# IMU.net
KiCad netlist of a schematic drawn in Altium Designer
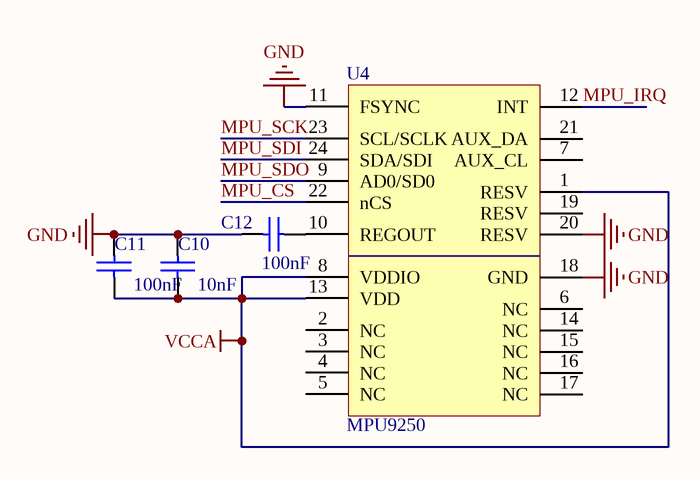
[diagram p0: IMU.SchDoc]

(export (version "E")
  (design (tool "Eeschema 10.0.6"))
  (components
    (comp (ref "C10")
      (value "10nF")
      (footprint "0402C")
      (description "贴片电阻")
      (libsource (lib "sparky") (part "cap"))
    )
    (comp (ref "C11")
      (value "100nF")
      (footprint "0402C")
      (description "贴片电阻")
      (libsource (lib "sparky") (part "cap"))
    )
    (comp (ref "C12")
      (value "100nF")
      (footprint "0402C")
      (description "贴片电阻")
      (libsource (lib "sparky") (part "cap"))
    )
    (comp (ref "U4") (value "MPU9250") (footprint "QFN24-0.4") (libsource (lib "MiniFly+") (part "MPU9250")))
  )
  (nets
    (net (code "1") (name "/MPU_CS") (class "Default")
      (node (ref "U4") (pin "22") (pinfunction "nCS_22") (pintype "passive"))
    )
    (net (code "2") (name "/MPU_IRQ") (class "Default")
      (node (ref "U4") (pin "12") (pinfunction "INT_12") (pintype "passive"))
    )
    (net (code "3") (name "/MPU_SCK") (class "Default")
      (node (ref "U4") (pin "23") (pinfunction "SCL/SCLK_23") (pintype "passive"))
    )
    (net (code "4") (name "/MPU_SDI") (class "Default")
      (node (ref "U4") (pin "24") (pinfunction "SDA/SDI_24") (pintype "passive"))
    )
    (net (code "5") (name "/MPU_SDO") (class "Default")
      (node (ref "U4") (pin "9") (pinfunction "AD0/SD0_9") (pintype "passive"))
    )
    (net (code "6") (name "GND") (class "Default")
      (node (ref "C10") (pin "2") (pinfunction "2_2") (pintype "passive"))
      (node (ref "C11") (pin "2") (pinfunction "2_2") (pintype "passive"))
      (node (ref "C12") (pin "1") (pinfunction "1_1") (pintype "passive"))
      (node (ref "U4") (pin "11") (pinfunction "FSYNC_11") (pintype "passive"))
      (node (ref "U4") (pin "18") (pinfunction "GND_18") (pintype "passive"))
      (node (ref "U4") (pin "20") (pinfunction "RESV_20") (pintype "passive"))
    )
    (net (code "7") (name "Net-(U4-REGOUT)") (class "Default")
      (node (ref "C12") (pin "2") (pinfunction "2_2") (pintype "passive"))
      (node (ref "U4") (pin "10") (pinfunction "REGOUT_10") (pintype "passive"))
    )
    (net (code "8") (name "VCCA") (class "Default")
      (node (ref "C10") (pin "1") (pinfunction "1_1") (pintype "passive"))
      (node (ref "C11") (pin "1") (pinfunction "1_1") (pintype "passive"))
      (node (ref "U4") (pin "1") (pinfunction "RESV_1") (pintype "passive"))
      (node (ref "U4") (pin "13") (pinfunction "VDD_13") (pintype "passive"))
      (node (ref "U4") (pin "8") (pinfunction "VDDIO_8") (pintype "passive"))
    )
    (net (code "9") (name "unconnected-(U4-AUX_CL-Pad7)") (class "Default")
      (node (ref "U4") (pin "7") (pinfunction "AUX_CL_7") (pintype "passive"))
    )
    (net (code "10") (name "unconnected-(U4-AUX_DA-Pad21)") (class "Default")
      (node (ref "U4") (pin "21") (pinfunction "AUX_DA_21") (pintype "passive"))
    )
    (net (code "11") (name "unconnected-(U4-NC-Pad2)") (class "Default")
      (node (ref "U4") (pin "2") (pinfunction "NC_2") (pintype "passive"))
    )
    (net (code "12") (name "unconnected-(U4-NC-Pad3)") (class "Default")
      (node (ref "U4") (pin "3") (pinfunction "NC_3") (pintype "passive"))
    )
    (net (code "13") (name "unconnected-(U4-NC-Pad4)") (class "Default")
      (node (ref "U4") (pin "4") (pinfunction "NC_4") (pintype "passive"))
    )
    (net (code "14") (name "unconnected-(U4-NC-Pad5)") (class "Default")
      (node (ref "U4") (pin "5") (pinfunction "NC_5") (pintype "passive"))
    )
    (net (code "15") (name "unconnected-(U4-NC-Pad6)") (class "Default")
      (node (ref "U4") (pin "6") (pinfunction "NC_6") (pintype "passive"))
    )
    (net (code "16") (name "unconnected-(U4-NC-Pad14)") (class "Default")
      (node (ref "U4") (pin "14") (pinfunction "NC_14") (pintype "passive"))
    )
    (net (code "17") (name "unconnected-(U4-NC-Pad15)") (class "Default")
      (node (ref "U4") (pin "15") (pinfunction "NC_15") (pintype "passive"))
    )
    (net (code "18") (name "unconnected-(U4-NC-Pad16)") (class "Default")
      (node (ref "U4") (pin "16") (pinfunction "NC_16") (pintype "passive"))
    )
    (net (code "19") (name "unconnected-(U4-NC-Pad17)") (class "Default")
      (node (ref "U4") (pin "17") (pinfunction "NC_17") (pintype "passive"))
    )
    (net (code "20") (name "unconnected-(U4-RESV-Pad19)") (class "Default")
      (node (ref "U4") (pin "19") (pinfunction "RESV_19") (pintype "passive"))
    )
  )
)
